# design.net
KiCad netlist of a schematic drawn in EasyEDA Pro
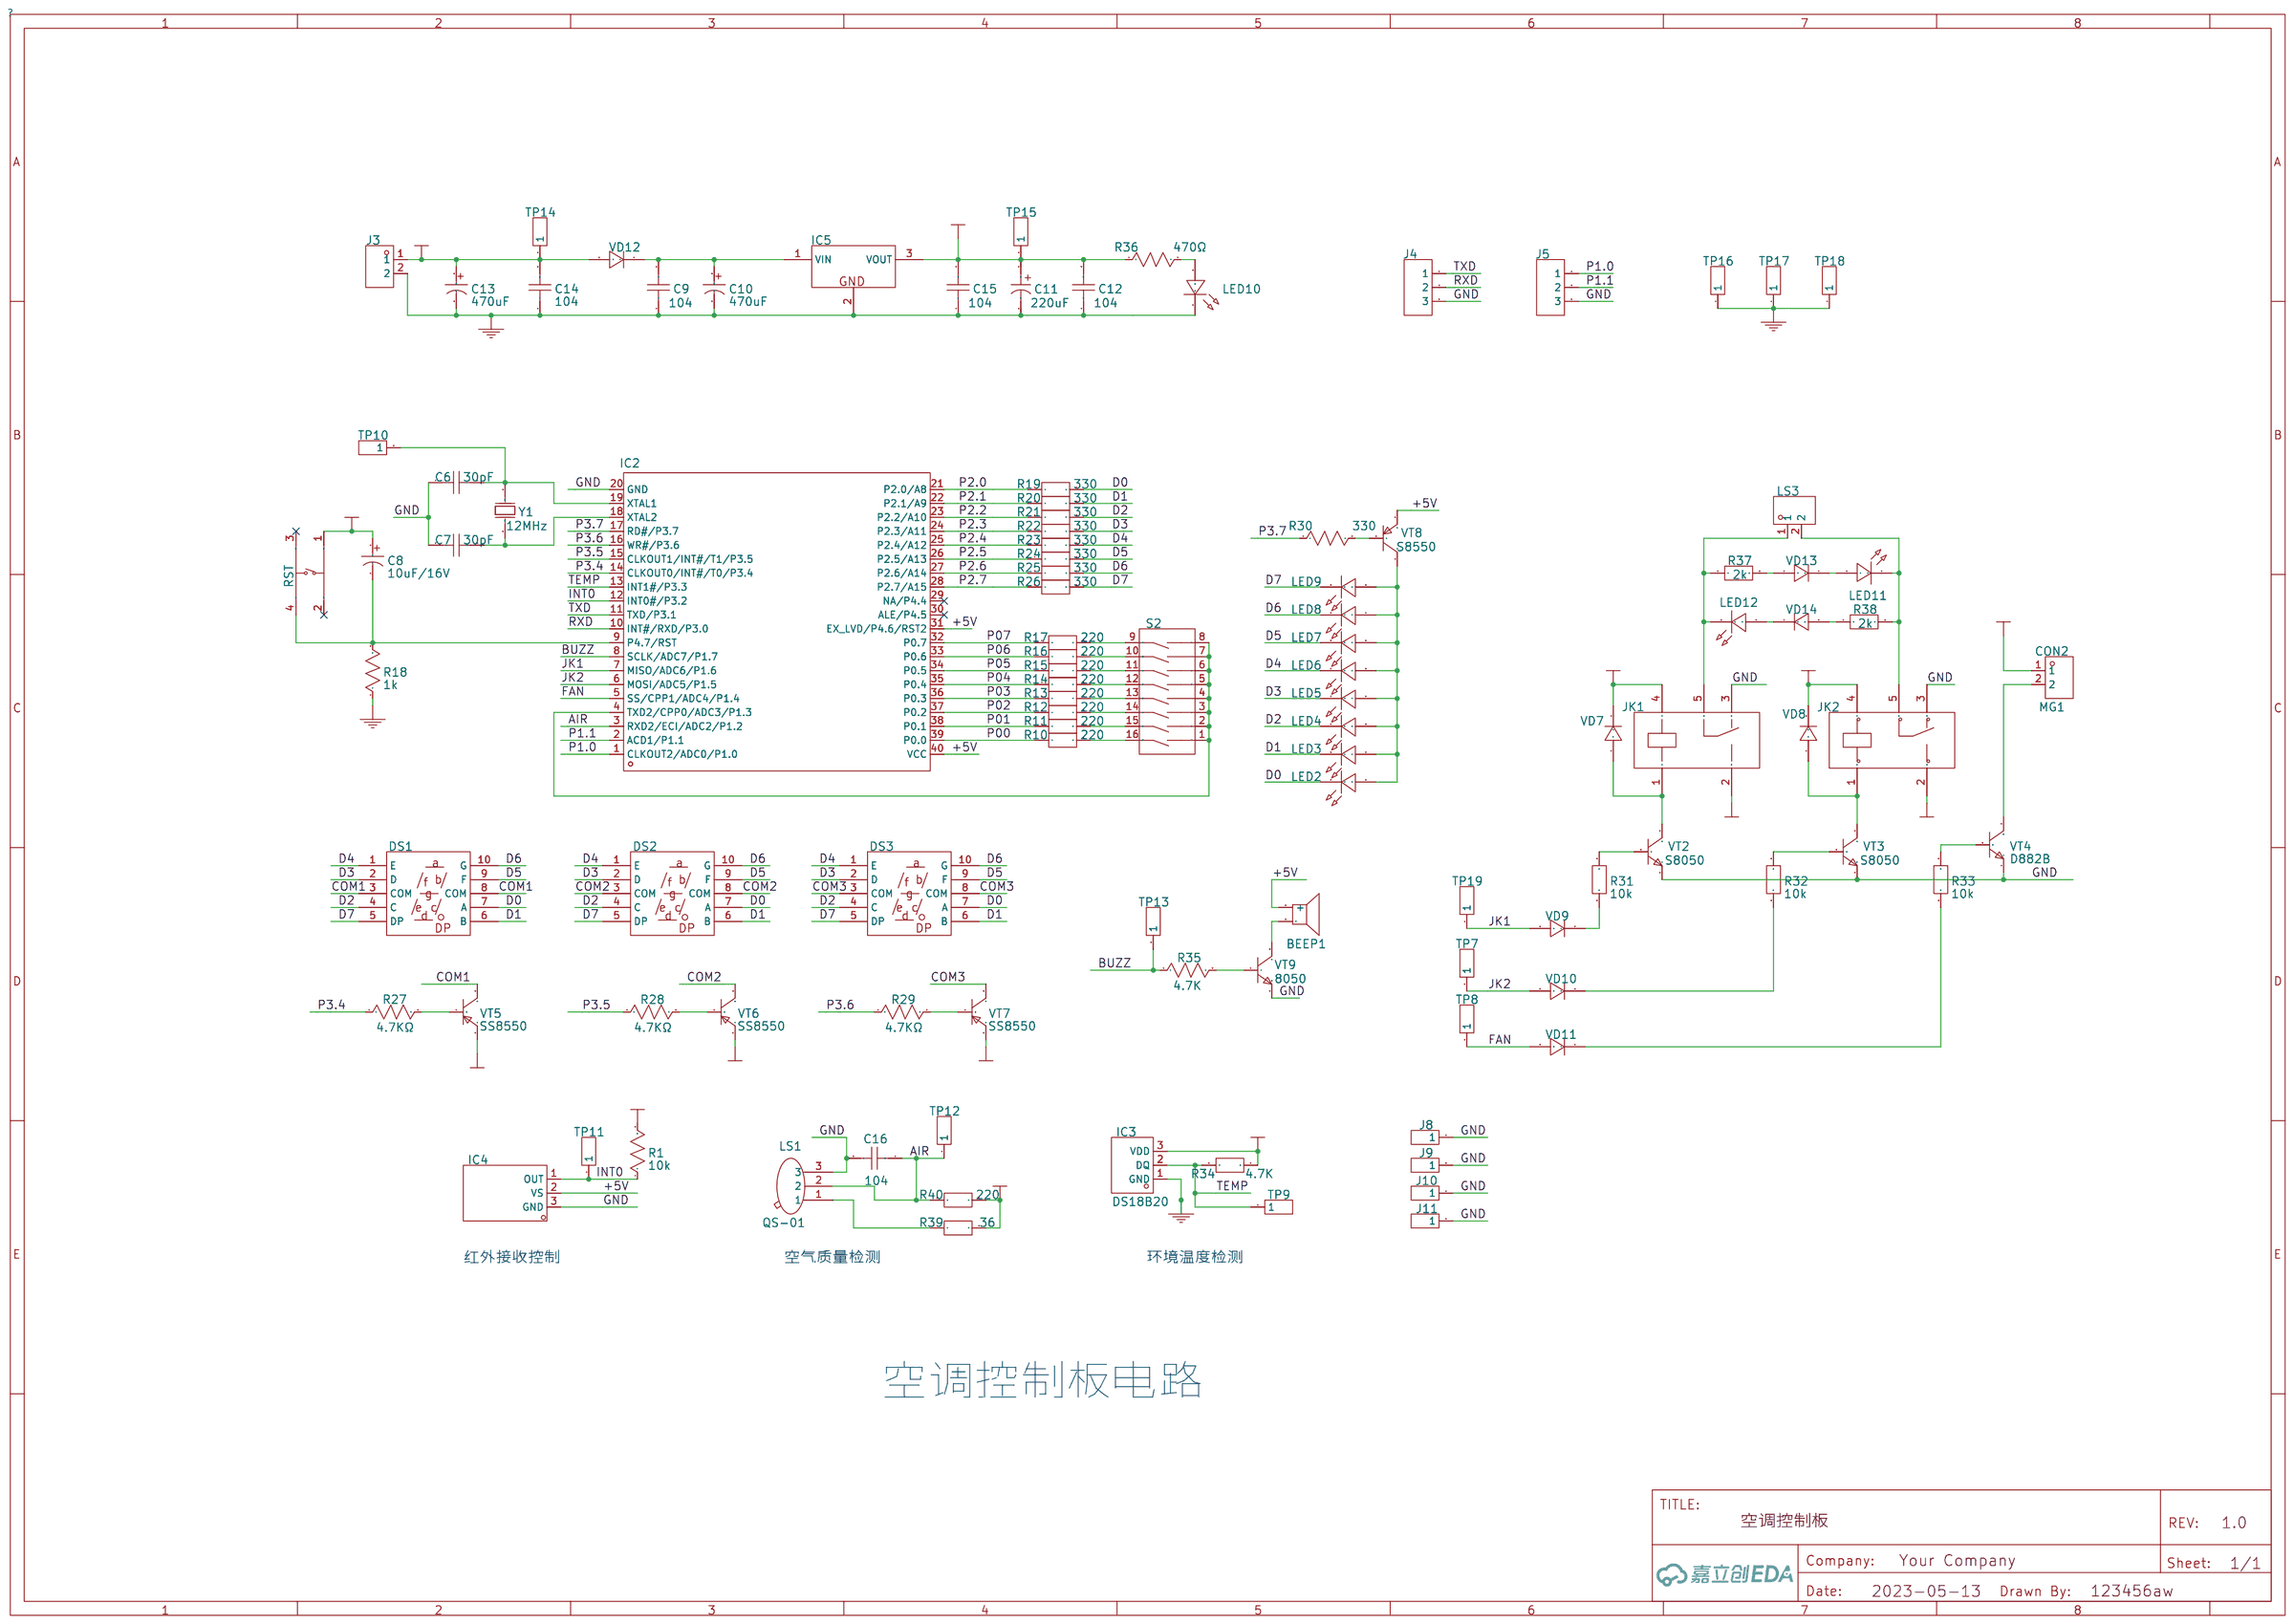
[diagram p0: schematic sheet]

(export (version "E")
  (design (tool "Eeschema 10.0.6"))
  (components
    (comp (ref "BEEP1")
      (value "TMB12A05")
      (footprint "easyedapro:BUZ-TH_BD12.0-P7.60-D0.6-FD")
      (fields (field (name "Manufacturer") "华能"))
      (libsource (lib "easyedapro") (part "TMB12A05"))
    )
    (comp (ref "C6")
      (value "30pF")
      (footprint "easyedapro:C0805")
      (libsource (lib "easyedapro") (part "30pF"))
    )
    (comp (ref "C7")
      (value "30pF")
      (footprint "easyedapro:C0805")
      (libsource (lib "easyedapro") (part "30pF"))
    )
    (comp (ref "C8")
      (value "10uF/16V")
      (footprint "easyedapro:CAP-TH_BD5.0-P2.5-D0.5-FD")
      (fields
        (field (name "Manufacturer Part") "RL1C100MC110A00CV0")
        (field (name "Manufacturer") "HUAWEI(华威集团)")
      )
      (libsource (lib "easyedapro") (part "10uF/16V"))
    )
    (comp (ref "C9") (value "104") (footprint "easyedapro:C0805") (libsource (lib "easyedapro") (part "104")))
    (comp (ref "C10")
      (value "470uF")
      (footprint "easyedapro:CAP-TH_BD10.0-P5.00-D1.0-FD")
      (fields
        (field (name "Manufacturer Part") "KM477M050G20RR0VH2FP0")
        (field (name "Manufacturer") "CX(承兴)")
      )
      (libsource (lib "easyedapro") (part "470uF"))
    )
    (comp (ref "C11")
      (value "220uF")
      (footprint "easyedapro:CAP-TH_BD8.0-P3.50-D0.6-FD_1")
      (fields (field (name "Manufacturer Part") "220uF/35V"))
      (libsource (lib "easyedapro") (part "220uF"))
    )
    (comp (ref "C12")
      (value "104")
      (footprint "easyedapro:C0805")
      (libsource (lib "easyedapro") (part "104"))
    )
    (comp (ref "C13")
      (value "470uF")
      (footprint "easyedapro:CAP-TH_BD10.0-P5.00-D1.0-FD")
      (fields
        (field (name "Manufacturer Part") "KM477M050G20RR0VH2FP0")
        (field (name "Manufacturer") "CX(承兴)")
      )
      (libsource (lib "easyedapro") (part "470uF"))
    )
    (comp (ref "C14")
      (value "104")
      (footprint "easyedapro:C0805")
      (libsource (lib "easyedapro") (part "104"))
    )
    (comp (ref "C15")
      (value "104")
      (footprint "easyedapro:C0805")
      (libsource (lib "easyedapro") (part "104"))
    )
    (comp (ref "C16")
      (value "104")
      (footprint "easyedapro:C0805")
      (libsource (lib "easyedapro") (part "104"))
    )
    (comp (ref "CON2")
      (value "MG1")
      (footprint "easyedapro:CONN-TH_XY301V-A-5.0-2P")
      (fields
        (field (name "Manufacturer Part") "XY301V-A-5.0-2P")
        (field (name "Manufacturer") "XINLAIYA(新莱亚)")
      )
      (libsource (lib "easyedapro") (part "MG1"))
    )
    (comp (ref "DS1")
      (value "FJ5101BH")
      (footprint "easyedapro:LED-SEG-TH_FJ5101BH")
      (fields (field (name "Manufacturer") "志浩"))
      (libsource (lib "easyedapro") (part "FJ5101BH"))
    )
    (comp (ref "DS2")
      (value "FJ5101BH")
      (footprint "easyedapro:LED-SEG-TH_FJ5101BH")
      (fields (field (name "Manufacturer") "志浩"))
      (libsource (lib "easyedapro") (part "FJ5101BH"))
    )
    (comp (ref "DS3")
      (value "FJ5101BH")
      (footprint "easyedapro:LED-SEG-TH_FJ5101BH")
      (fields (field (name "Manufacturer") "志浩"))
      (libsource (lib "easyedapro") (part "FJ5101BH"))
    )
    (comp (ref "IC2")
      (value "STC12C5A32S2")
      (footprint "easyedapro:DIP-40_L52.3-W13.9-P2.54-LS15.2-BL")
      (fields
        (field (name "Manufacturer Part") "STC12C5A32S2-35I-PDIP40")
        (field (name "Manufacturer") "STC(宏晶)")
      )
      (libsource (lib "easyedapro") (part "STC12C5A32S2"))
    )
    (comp (ref "IC3")
      (value "DS18B20")
      (footprint "easyedapro:TO-92-3_L4.9-W3.7-P1.27-L")
      (fields (field (name "Manufacturer") "UMW(广东友台半导体)"))
      (libsource (lib "easyedapro") (part "DS18B20"))
    )
    (comp (ref "IC4")
      (value "TSOP31256")
      (footprint "easyedapro:红外接收管封装")
      (fields (field (name "Manufacturer") "VISHAY(威世)"))
      (libsource (lib "easyedapro") (part "TSOP31256"))
    )
    (comp (ref "IC5")
      (value "LM7805CT_C5444281")
      (footprint "easyedapro:三端稳压器LM7805")
      (fields (field (name "Manufacturer Part") "LM7805CT") (field (name "Manufacturer") "Siproin(上海矽朋)"))
      (libsource (lib "easyedapro") (part "LM7805CT_C5444281"))
    )
    (comp (ref "J3")
      (value "GND   +12V")
      (footprint "easyedapro:CONN-TH_XY301V-A-5.0-2P")
      (fields
        (field (name "Manufacturer Part") "XY301V-A-5.0-2P")
        (field (name "Manufacturer") "XINLAIYA(新莱亚)")
      )
      (libsource (lib "easyedapro") (part "GND   +12V"))
    )
    (comp (ref "J4")
      (value "TXD RXD GND")
      (footprint "easyedapro:HDR-F-2.54_1X3")
      (libsource (lib "easyedapro") (part "TXD RXD GND"))
    )
    (comp (ref "J5")
      (value "HDR-F-2.54_1x3")
      (footprint "easyedapro:HDR-F-2.54_1X3")
      (libsource (lib "easyedapro") (part "HDR-F-2.54_1x3"))
    )
    (comp (ref "J8") (value "RS") (footprint "easyedapro:焊盘M3") (libsource (lib "easyedapro") (part "RS")))
    (comp (ref "J9") (value "RS") (footprint "easyedapro:焊盘M3") (libsource (lib "easyedapro") (part "RS")))
    (comp (ref "J10") (value "RS") (footprint "easyedapro:焊盘M3") (libsource (lib "easyedapro") (part "RS")))
    (comp (ref "J11") (value "RS") (footprint "easyedapro:焊盘M3") (libsource (lib "easyedapro") (part "RS")))
    (comp (ref "JK1")
      (value "SRD-12VDC-SL-C")
      (footprint "easyedapro:RELAY-TH_SRD-XXVDC-XL-C")
      (fields (field (name "Manufacturer") "松乐"))
      (libsource (lib "easyedapro") (part "SRD-12VDC-SL-C"))
    )
    (comp (ref "JK2")
      (value "SRD-12VDC-SL-C")
      (footprint "easyedapro:RELAY-TH_SRD-XXVDC-XL-C")
      (fields (field (name "Manufacturer") "松乐"))
      (libsource (lib "") (part "SRD-12VDC-SL-C_1"))
    )
    (comp (ref "LED2")
      (value "LED-0805_R")
      (footprint "easyedapro:LED0805_RED")
      (fields
        (field (name "Manufacturer Part") "17-21SURC/S530-A3/TR8")
        (field (name "Manufacturer") "EVERLIGHT(台湾亿光)")
      )
      (libsource (lib "easyedapro") (part "LED-0805_R"))
    )
    (comp (ref "LED3")
      (value "LED-0805_R")
      (footprint "easyedapro:LED0805_RED")
      (fields
        (field (name "Manufacturer Part") "17-21SURC/S530-A3/TR8")
        (field (name "Manufacturer") "EVERLIGHT(台湾亿光)")
      )
      (libsource (lib "easyedapro") (part "LED-0805_R"))
    )
    (comp (ref "LED4")
      (value "LED-0805_R")
      (footprint "easyedapro:LED0805_RED")
      (fields
        (field (name "Manufacturer Part") "17-21SURC/S530-A3/TR8")
        (field (name "Manufacturer") "EVERLIGHT(台湾亿光)")
      )
      (libsource (lib "easyedapro") (part "LED-0805_R"))
    )
    (comp (ref "LED5")
      (value "LED-0805_R")
      (footprint "easyedapro:LED0805_RED")
      (fields
        (field (name "Manufacturer Part") "17-21SURC/S530-A3/TR8")
        (field (name "Manufacturer") "EVERLIGHT(台湾亿光)")
      )
      (libsource (lib "easyedapro") (part "LED-0805_R"))
    )
    (comp (ref "LED6")
      (value "LED-0805_R")
      (footprint "easyedapro:LED0805_RED")
      (fields
        (field (name "Manufacturer Part") "17-21SURC/S530-A3/TR8")
        (field (name "Manufacturer") "EVERLIGHT(台湾亿光)")
      )
      (libsource (lib "easyedapro") (part "LED-0805_R"))
    )
    (comp (ref "LED7")
      (value "LED-0805_R")
      (footprint "easyedapro:LED0805_RED")
      (fields
        (field (name "Manufacturer Part") "17-21SURC/S530-A3/TR8")
        (field (name "Manufacturer") "EVERLIGHT(台湾亿光)")
      )
      (libsource (lib "easyedapro") (part "LED-0805_R"))
    )
    (comp (ref "LED8")
      (value "LED-0805_R")
      (footprint "easyedapro:LED0805_RED")
      (fields
        (field (name "Manufacturer Part") "17-21SURC/S530-A3/TR8")
        (field (name "Manufacturer") "EVERLIGHT(台湾亿光)")
      )
      (libsource (lib "easyedapro") (part "LED-0805_R"))
    )
    (comp (ref "LED9")
      (value "LED-0805_R")
      (footprint "easyedapro:LED0805_RED")
      (fields
        (field (name "Manufacturer Part") "17-21SURC/S530-A3/TR8")
        (field (name "Manufacturer") "EVERLIGHT(台湾亿光)")
      )
      (libsource (lib "easyedapro") (part "LED-0805_R"))
    )
    (comp (ref "LED10")
      (value "LED-0805_R")
      (footprint "easyedapro:LED0805_RED")
      (fields
        (field (name "Manufacturer Part") "17-21SURC/S530-A3/TR8")
        (field (name "Manufacturer") "EVERLIGHT(台湾亿光)")
      )
      (libsource (lib "easyedapro") (part "LED-0805_R"))
    )
    (comp (ref "LED11")
      (value "LED-0805_R")
      (footprint "easyedapro:LED0805_RED")
      (fields
        (field (name "Manufacturer Part") "17-21SURC/S530-A3/TR8")
        (field (name "Manufacturer") "EVERLIGHT(台湾亿光)")
      )
      (libsource (lib "easyedapro") (part "LED-0805_R"))
    )
    (comp (ref "LED12")
      (value "LED-0805_R")
      (footprint "easyedapro:LED0805_RED")
      (fields
        (field (name "Manufacturer Part") "17-21SURC/S530-A3/TR8")
        (field (name "Manufacturer") "EVERLIGHT(台湾亿光)")
      )
      (libsource (lib "easyedapro") (part "LED-0805_R"))
    )
    (comp (ref "LS1")
      (value "QS-01")
      (footprint "easyedapro:空气质量传感器")
      (fields (field (name "Manufacturer Part") "MP901") (field (name "Manufacturer") "Winsen(炜盛)"))
      (libsource (lib "easyedapro") (part "QS-01"))
    )
    (comp (ref "LS3")
      (value "XY301V-A-5.0-2P")
      (footprint "easyedapro:CONN-TH_XY301V-A-5.0-2P")
      (fields (field (name "Manufacturer") "XINLAIYA(新莱亚)"))
      (libsource (lib "easyedapro") (part "XY301V-A-5.0-2P"))
    )
    (comp (ref "R1") (value "10k") (footprint "easyedapro:R0805") (libsource (lib "") (part "10k_1")))
    (comp (ref "R10")
      (value "220")
      (footprint "easyedapro:R0805")
      (libsource (lib "easyedapro") (part "220"))
    )
    (comp (ref "R11")
      (value "220")
      (footprint "easyedapro:R0805")
      (libsource (lib "easyedapro") (part "220"))
    )
    (comp (ref "R12")
      (value "220")
      (footprint "easyedapro:R0805")
      (libsource (lib "easyedapro") (part "220"))
    )
    (comp (ref "R13")
      (value "220")
      (footprint "easyedapro:R0805")
      (libsource (lib "easyedapro") (part "220"))
    )
    (comp (ref "R14")
      (value "220")
      (footprint "easyedapro:R0805")
      (libsource (lib "easyedapro") (part "220"))
    )
    (comp (ref "R15")
      (value "220")
      (footprint "easyedapro:R0805")
      (libsource (lib "easyedapro") (part "220"))
    )
    (comp (ref "R16")
      (value "220")
      (footprint "easyedapro:R0805")
      (libsource (lib "easyedapro") (part "220"))
    )
    (comp (ref "R17")
      (value "220")
      (footprint "easyedapro:R0805")
      (libsource (lib "easyedapro") (part "220"))
    )
    (comp (ref "R18") (value "1k") (footprint "easyedapro:R0805") (libsource (lib "easyedapro") (part "1k")))
    (comp (ref "R19")
      (value "330")
      (footprint "easyedapro:R0805")
      (libsource (lib "easyedapro") (part "330"))
    )
    (comp (ref "R20")
      (value "330")
      (footprint "easyedapro:R0805")
      (libsource (lib "easyedapro") (part "330"))
    )
    (comp (ref "R21")
      (value "330")
      (footprint "easyedapro:R0805")
      (libsource (lib "easyedapro") (part "330"))
    )
    (comp (ref "R22")
      (value "330")
      (footprint "easyedapro:R0805")
      (libsource (lib "easyedapro") (part "330"))
    )
    (comp (ref "R23")
      (value "330")
      (footprint "easyedapro:R0805")
      (libsource (lib "easyedapro") (part "330"))
    )
    (comp (ref "R24")
      (value "330")
      (footprint "easyedapro:R0805")
      (libsource (lib "easyedapro") (part "330"))
    )
    (comp (ref "R25")
      (value "330")
      (footprint "easyedapro:R0805")
      (libsource (lib "easyedapro") (part "330"))
    )
    (comp (ref "R26")
      (value "330")
      (footprint "easyedapro:R0805")
      (libsource (lib "easyedapro") (part "330"))
    )
    (comp (ref "R27")
      (value "4.7KΩ")
      (footprint "easyedapro:R0805")
      (libsource (lib "easyedapro") (part "4.7KΩ"))
    )
    (comp (ref "R28")
      (value "4.7KΩ")
      (footprint "easyedapro:R0805")
      (libsource (lib "easyedapro") (part "4.7KΩ"))
    )
    (comp (ref "R29")
      (value "4.7KΩ")
      (footprint "easyedapro:R0805")
      (libsource (lib "easyedapro") (part "4.7KΩ"))
    )
    (comp (ref "R30") (value "330") (footprint "easyedapro:R0805") (libsource (lib "") (part "330_1")))
    (comp (ref "R31")
      (value "10k")
      (footprint "easyedapro:R0805")
      (libsource (lib "easyedapro") (part "10k"))
    )
    (comp (ref "R32")
      (value "10k")
      (footprint "easyedapro:R0805")
      (libsource (lib "easyedapro") (part "10k"))
    )
    (comp (ref "R33")
      (value "10k")
      (footprint "easyedapro:R0805")
      (libsource (lib "easyedapro") (part "10k"))
    )
    (comp (ref "R34") (value "4.7K") (footprint "easyedapro:R0805") (libsource (lib "") (part "4.7K_1")))
    (comp (ref "R35")
      (value "4.7K")
      (footprint "easyedapro:R0805")
      (libsource (lib "easyedapro") (part "4.7K"))
    )
    (comp (ref "R36")
      (value "470Ω")
      (footprint "easyedapro:R0805")
      (libsource (lib "easyedapro") (part "470Ω"))
    )
    (comp (ref "R37") (value "2k") (footprint "easyedapro:R0805") (libsource (lib "easyedapro") (part "2k")))
    (comp (ref "R38") (value "2k") (footprint "easyedapro:R0805") (libsource (lib "easyedapro") (part "2k")))
    (comp (ref "R39")
      (value "36")
      (footprint "easyedapro:R2010")
      (fields
        (field (name "Manufacturer Part") "201007F360JT4E")
        (field (name "Manufacturer") "UNI-ROYAL(厚声)")
      )
      (libsource (lib "easyedapro") (part "36"))
    )
    (comp (ref "R40")
      (value "220")
      (footprint "easyedapro:R0805")
      (libsource (lib "easyedapro") (part "220"))
    )
    (comp (ref "RST")
      (value "TS665CJ")
      (footprint "easyedapro:SW-TH_4P-L6.0-W6.0-P4.50-LS6.5")
      (fields (field (name "Manufacturer") "SHOU HAN(首韩)"))
      (libsource (lib "easyedapro") (part "TS665CJ"))
    )
    (comp (ref "S2")
      (value "2.54插件8位拨码开关")
      (footprint "easyedapro:SW-TH_16P-L21.9-W9.9-P2.54-LS7.8")
      (libsource (lib "easyedapro") (part "2.54插件8位拨码开关"))
    )
    (comp (ref "TP7")
      (value "HDR-M-2.54_1x1")
      (footprint "easyedapro:HDR-M-2.54_1X1")
      (libsource (lib "easyedapro") (part "HDR-M-2.54_1x1"))
    )
    (comp (ref "TP8")
      (value "HDR-M-2.54_1x1")
      (footprint "easyedapro:HDR-M-2.54_1X1")
      (libsource (lib "easyedapro") (part "HDR-M-2.54_1x1"))
    )
    (comp (ref "TP9")
      (value "HDR-M-2.54_1x1")
      (footprint "easyedapro:HDR-M-2.54_1X1")
      (libsource (lib "easyedapro") (part "HDR-M-2.54_1x1"))
    )
    (comp (ref "TP10")
      (value "HDR-M-2.54_1x1")
      (footprint "easyedapro:HDR-M-2.54_1X1")
      (libsource (lib "easyedapro") (part "HDR-M-2.54_1x1"))
    )
    (comp (ref "TP11")
      (value "HDR-M-2.54_1x1")
      (footprint "easyedapro:HDR-M-2.54_1X1")
      (libsource (lib "easyedapro") (part "HDR-M-2.54_1x1"))
    )
    (comp (ref "TP12")
      (value "HDR-M-2.54_1x1")
      (footprint "easyedapro:HDR-M-2.54_1X1")
      (libsource (lib "easyedapro") (part "HDR-M-2.54_1x1"))
    )
    (comp (ref "TP13")
      (value "HDR-M-2.54_1x1")
      (footprint "easyedapro:HDR-M-2.54_1X1")
      (libsource (lib "easyedapro") (part "HDR-M-2.54_1x1"))
    )
    (comp (ref "TP14")
      (value "HDR-M-2.54_1x1")
      (footprint "easyedapro:HDR-M-2.54_1X1")
      (libsource (lib "easyedapro") (part "HDR-M-2.54_1x1"))
    )
    (comp (ref "TP15")
      (value "HDR-M-2.54_1x1")
      (footprint "easyedapro:HDR-M-2.54_1X1")
      (libsource (lib "easyedapro") (part "HDR-M-2.54_1x1"))
    )
    (comp (ref "TP16")
      (value "HDR-M-2.54_1x1")
      (footprint "easyedapro:HDR-M-2.54_1X1")
      (libsource (lib "easyedapro") (part "HDR-M-2.54_1x1"))
    )
    (comp (ref "TP17")
      (value "HDR-M-2.54_1x1")
      (footprint "easyedapro:HDR-M-2.54_1X1")
      (libsource (lib "easyedapro") (part "HDR-M-2.54_1x1"))
    )
    (comp (ref "TP18")
      (value "HDR-M-2.54_1x1")
      (footprint "easyedapro:HDR-M-2.54_1X1")
      (libsource (lib "easyedapro") (part "HDR-M-2.54_1x1"))
    )
    (comp (ref "TP19")
      (value "HDR-M-2.54_1x1")
      (footprint "easyedapro:HDR-M-2.54_1X1")
      (libsource (lib "easyedapro") (part "HDR-M-2.54_1x1"))
    )
    (comp (ref "VD7")
      (value "1N4007G_C189227")
      (footprint "easyedapro:DO-41_BD2.4-L4.7-P8.70-D0.9-RD")
      (fields (field (name "Manufacturer Part") "1N4007G") (field (name "Manufacturer") "迪一"))
      (libsource (lib "easyedapro") (part "1N4007G_C189227"))
    )
    (comp (ref "VD8")
      (value "1N4007G_C189227")
      (footprint "easyedapro:DO-41_BD2.4-L4.7-P8.70-D0.9-RD")
      (fields (field (name "Manufacturer Part") "1N4007G") (field (name "Manufacturer") "迪一"))
      (libsource (lib "easyedapro") (part "1N4007G_C189227"))
    )
    (comp (ref "VD9")
      (value "1N4007G_C189227")
      (footprint "easyedapro:DO-41_BD2.4-L4.7-P8.70-D0.9-RD")
      (fields (field (name "Manufacturer Part") "1N4007G") (field (name "Manufacturer") "迪一"))
      (libsource (lib "easyedapro") (part "1N4007G_C189227"))
    )
    (comp (ref "VD10")
      (value "1N4007G_C189227")
      (footprint "easyedapro:DO-41_BD2.4-L4.7-P8.70-D0.9-RD")
      (fields (field (name "Manufacturer Part") "1N4007G") (field (name "Manufacturer") "迪一"))
      (libsource (lib "easyedapro") (part "1N4007G_C189227"))
    )
    (comp (ref "VD11")
      (value "1N4007G_C189227")
      (footprint "easyedapro:DO-41_BD2.4-L4.7-P8.70-D0.9-RD")
      (fields (field (name "Manufacturer Part") "1N4007G") (field (name "Manufacturer") "迪一"))
      (libsource (lib "easyedapro") (part "1N4007G_C189227"))
    )
    (comp (ref "VD12")
      (value "1N4007G_C189227")
      (footprint "easyedapro:DO-41_BD2.4-L4.7-P8.70-D0.9-RD")
      (fields (field (name "Manufacturer Part") "1N4007G") (field (name "Manufacturer") "迪一"))
      (libsource (lib "easyedapro") (part "1N4007G_C189227"))
    )
    (comp (ref "VD13")
      (value "1N4007G_C189227")
      (footprint "easyedapro:DO-41_BD2.4-L4.7-P8.70-D0.9-RD")
      (fields (field (name "Manufacturer Part") "1N4007G") (field (name "Manufacturer") "迪一"))
      (libsource (lib "easyedapro") (part "1N4007G_C189227"))
    )
    (comp (ref "VD14")
      (value "1N4007G_C189227")
      (footprint "easyedapro:DO-41_BD2.4-L4.7-P8.70-D0.9-RD")
      (fields (field (name "Manufacturer Part") "1N4007G") (field (name "Manufacturer") "迪一"))
      (libsource (lib "easyedapro") (part "1N4007G_C189227"))
    )
    (comp (ref "VT2")
      (value "S8050")
      (footprint "easyedapro:SOT-23-3_L2.9-W1.6-P1.90-LS2.8-BR")
      (fields (field (name "Manufacturer") "Hottech(合科泰)"))
      (libsource (lib "easyedapro") (part "S8050"))
    )
    (comp (ref "VT3")
      (value "S8050")
      (footprint "easyedapro:SOT-23-3_L2.9-W1.6-P1.90-LS2.8-BR")
      (fields (field (name "Manufacturer") "Hottech(合科泰)"))
      (libsource (lib "easyedapro") (part "S8050"))
    )
    (comp (ref "VT4")
      (value "D882B")
      (footprint "easyedapro:TO-126_L7.8-W2.7-P2.30-L")
      (fields (field (name "Manufacturer") "FeiHong(飞虹)"))
      (libsource (lib "easyedapro") (part "D882B"))
    )
    (comp (ref "VT5")
      (value "SS8550")
      (footprint "easyedapro:SOT-23-3_L2.9-W1.3-P1.90-LS2.4-BR")
      (fields (field (name "Manufacturer Part") "SS8550-MS") (field (name "Manufacturer") "MSKSEMI(美森科)"))
      (libsource (lib "easyedapro") (part "SS8550"))
    )
    (comp (ref "VT6")
      (value "SS8550")
      (footprint "easyedapro:SOT-23-3_L2.9-W1.3-P1.90-LS2.4-BR")
      (fields (field (name "Manufacturer Part") "SS8550-MS") (field (name "Manufacturer") "MSKSEMI(美森科)"))
      (libsource (lib "easyedapro") (part "SS8550"))
    )
    (comp (ref "VT7")
      (value "SS8550")
      (footprint "easyedapro:SOT-23-3_L2.9-W1.3-P1.90-LS2.4-BR")
      (fields (field (name "Manufacturer Part") "SS8550-MS") (field (name "Manufacturer") "MSKSEMI(美森科)"))
      (libsource (lib "easyedapro") (part "SS8550"))
    )
    (comp (ref "VT8")
      (value "S8550")
      (footprint "easyedapro:SOT-23-3_L2.9-W1.6-P1.90-LS2.8-BR")
      (fields (field (name "Manufacturer") "CJ(江苏长电/长晶)"))
      (libsource (lib "easyedapro") (part "S8550"))
    )
    (comp (ref "VT9")
      (value "8050")
      (footprint "easyedapro:SOT-23-3_L2.9-W1.6-P1.90-LS2.8-BR")
      (fields (field (name "Manufacturer Part") "S9013") (field (name "Manufacturer") "CJ(江苏长电/长晶)"))
      (libsource (lib "easyedapro") (part "8050"))
    )
    (comp (ref "Y1")
      (value "12MHz")
      (footprint "easyedapro:HC-49US_L11.5-W4.5-P4.88")
      (fields (field (name "Manufacturer Part") "X49SD12MSD2SC") (field (name "Manufacturer") "YXC(扬兴晶振)"))
      (libsource (lib "easyedapro") (part "12MHz"))
    )
  )
  (nets
    (net (code "1") (name "+5V") (class "Default")
      (node (ref "BEEP1") (pin "1") (pinfunction "+_1") (pintype "input"))
      (node (ref "C11") (pin "1") (pinfunction "1_1") (pintype "input"))
      (node (ref "C12") (pin "2") (pinfunction "2_2") (pintype "input"))
      (node (ref "C15") (pin "2") (pinfunction "2_2") (pintype "input"))
      (node (ref "C8") (pin "1") (pinfunction "1_1") (pintype "input"))
      (node (ref "IC2") (pin "31") (pinfunction "EX_LVD/P4.6/RST2_31") (pintype "input"))
      (node (ref "IC2") (pin "40") (pinfunction "VCC_40") (pintype "input"))
      (node (ref "IC3") (pin "3") (pinfunction "VDD_3") (pintype "input"))
      (node (ref "IC4") (pin "2") (pinfunction "VS_2") (pintype "input"))
      (node (ref "IC5") (pin "3") (pinfunction "VOUT_3") (pintype "input"))
      (node (ref "R1") (pin "2") (pinfunction "2_2") (pintype "input"))
      (node (ref "R34") (pin "1") (pinfunction "1_1") (pintype "input"))
      (node (ref "R36") (pin "1") (pinfunction "1_1") (pintype "input"))
      (node (ref "R39") (pin "2") (pinfunction "2_2") (pintype "input"))
      (node (ref "R40") (pin "2") (pinfunction "2_2") (pintype "input"))
      (node (ref "RST") (pin "1") (pinfunction "A_1") (pintype "input"))
      (node (ref "TP15") (pin "1") (pinfunction "1_1") (pintype "input"))
      (node (ref "VT5") (pin "2") (pinfunction "E_2") (pintype "input"))
      (node (ref "VT6") (pin "2") (pinfunction "E_2") (pintype "input"))
      (node (ref "VT7") (pin "2") (pinfunction "E_2") (pintype "input"))
      (node (ref "VT8") (pin "2") (pinfunction "2_2") (pintype "input"))
    )
    (net (code "2") (name "+12V") (class "Default")
      (node (ref "C13") (pin "1") (pinfunction "1_1") (pintype "input"))
      (node (ref "C14") (pin "2") (pinfunction "2_2") (pintype "input"))
      (node (ref "CON2") (pin "1") (pinfunction "1_1") (pintype "input"))
      (node (ref "J3") (pin "1") (pinfunction "1_1") (pintype "input"))
      (node (ref "JK1") (pin "2") (pinfunction "2_2") (pintype "input"))
      (node (ref "JK1") (pin "4") (pinfunction "4_4") (pintype "input"))
      (node (ref "JK2") (pin "2") (pinfunction "2_2") (pintype "input"))
      (node (ref "JK2") (pin "4") (pinfunction "4_4") (pintype "input"))
      (node (ref "TP14") (pin "1") (pinfunction "1_1") (pintype "input"))
      (node (ref "VD12") (pin "2") (pinfunction "2_2") (pintype "input"))
      (node (ref "VD7") (pin "1") (pinfunction "1_1") (pintype "input"))
      (node (ref "VD8") (pin "1") (pinfunction "1_1") (pintype "input"))
    )
    (net (code "3") (name "/AIR") (class "Default")
      (node (ref "C16") (pin "1") (pinfunction "1_1") (pintype "input"))
      (node (ref "IC2") (pin "3") (pinfunction "RXD2/ECI/ADC2/P1.2_3") (pintype "input"))
      (node (ref "LS1") (pin "2") (pinfunction "2_2") (pintype "input"))
      (node (ref "R40") (pin "1") (pinfunction "1_1") (pintype "input"))
      (node (ref "TP12") (pin "1") (pinfunction "1_1") (pintype "input"))
    )
    (net (code "4") (name "/BUZZ") (class "Default")
      (node (ref "IC2") (pin "8") (pinfunction "SCLK/ADC7/P1.7_8") (pintype "input"))
      (node (ref "R35") (pin "1") (pinfunction "1_1") (pintype "input"))
      (node (ref "TP13") (pin "1") (pinfunction "1_1") (pintype "input"))
    )
    (net (code "5") (name "/COM1") (class "Default")
      (node (ref "DS1") (pin "3") (pinfunction "COM_3") (pintype "input"))
      (node (ref "DS1") (pin "8") (pinfunction "COM_8") (pintype "input"))
      (node (ref "VT5") (pin "3") (pinfunction "C_3") (pintype "input"))
    )
    (net (code "6") (name "/COM2") (class "Default")
      (node (ref "DS2") (pin "3") (pinfunction "COM_3") (pintype "input"))
      (node (ref "DS2") (pin "8") (pinfunction "COM_8") (pintype "input"))
      (node (ref "VT6") (pin "3") (pinfunction "C_3") (pintype "input"))
    )
    (net (code "7") (name "/COM3") (class "Default")
      (node (ref "DS3") (pin "3") (pinfunction "COM_3") (pintype "input"))
      (node (ref "DS3") (pin "8") (pinfunction "COM_8") (pintype "input"))
      (node (ref "VT7") (pin "3") (pinfunction "C_3") (pintype "input"))
    )
    (net (code "8") (name "/D0") (class "Default")
      (node (ref "DS1") (pin "7") (pinfunction "A_7") (pintype "input"))
      (node (ref "DS2") (pin "7") (pinfunction "A_7") (pintype "input"))
      (node (ref "DS3") (pin "7") (pinfunction "A_7") (pintype "input"))
      (node (ref "LED2") (pin "2") (pinfunction "2_2") (pintype "input"))
      (node (ref "R19") (pin "2") (pinfunction "2_2") (pintype "input"))
    )
    (net (code "9") (name "/D1") (class "Default")
      (node (ref "DS1") (pin "6") (pinfunction "B_6") (pintype "input"))
      (node (ref "DS2") (pin "6") (pinfunction "B_6") (pintype "input"))
      (node (ref "DS3") (pin "6") (pinfunction "B_6") (pintype "input"))
      (node (ref "LED3") (pin "2") (pinfunction "2_2") (pintype "input"))
      (node (ref "R20") (pin "2") (pinfunction "2_2") (pintype "input"))
    )
    (net (code "10") (name "/D2") (class "Default")
      (node (ref "DS1") (pin "4") (pinfunction "C_4") (pintype "input"))
      (node (ref "DS2") (pin "4") (pinfunction "C_4") (pintype "input"))
      (node (ref "DS3") (pin "4") (pinfunction "C_4") (pintype "input"))
      (node (ref "LED4") (pin "2") (pinfunction "2_2") (pintype "input"))
      (node (ref "R21") (pin "2") (pinfunction "2_2") (pintype "input"))
    )
    (net (code "11") (name "/D3") (class "Default")
      (node (ref "DS1") (pin "2") (pinfunction "D_2") (pintype "input"))
      (node (ref "DS2") (pin "2") (pinfunction "D_2") (pintype "input"))
      (node (ref "DS3") (pin "2") (pinfunction "D_2") (pintype "input"))
      (node (ref "LED5") (pin "2") (pinfunction "2_2") (pintype "input"))
      (node (ref "R22") (pin "2") (pinfunction "2_2") (pintype "input"))
    )
    (net (code "12") (name "/D4") (class "Default")
      (node (ref "DS1") (pin "1") (pinfunction "E_1") (pintype "input"))
      (node (ref "DS2") (pin "1") (pinfunction "E_1") (pintype "input"))
      (node (ref "DS3") (pin "1") (pinfunction "E_1") (pintype "input"))
      (node (ref "LED6") (pin "2") (pinfunction "2_2") (pintype "input"))
      (node (ref "R23") (pin "2") (pinfunction "2_2") (pintype "input"))
    )
    (net (code "13") (name "/D5") (class "Default")
      (node (ref "DS1") (pin "9") (pinfunction "F_9") (pintype "input"))
      (node (ref "DS2") (pin "9") (pinfunction "F_9") (pintype "input"))
      (node (ref "DS3") (pin "9") (pinfunction "F_9") (pintype "input"))
      (node (ref "LED7") (pin "2") (pinfunction "2_2") (pintype "input"))
      (node (ref "R24") (pin "2") (pinfunction "2_2") (pintype "input"))
    )
    (net (code "14") (name "/D6") (class "Default")
      (node (ref "DS1") (pin "10") (pinfunction "G_10") (pintype "input"))
      (node (ref "DS2") (pin "10") (pinfunction "G_10") (pintype "input"))
      (node (ref "DS3") (pin "10") (pinfunction "G_10") (pintype "input"))
      (node (ref "LED8") (pin "2") (pinfunction "2_2") (pintype "input"))
      (node (ref "R25") (pin "2") (pinfunction "2_2") (pintype "input"))
    )
    (net (code "15") (name "/D7") (class "Default")
      (node (ref "DS1") (pin "5") (pinfunction "DP_5") (pintype "input"))
      (node (ref "DS2") (pin "5") (pinfunction "DP_5") (pintype "input"))
      (node (ref "DS3") (pin "5") (pinfunction "DP_5") (pintype "input"))
      (node (ref "LED9") (pin "2") (pinfunction "2_2") (pintype "input"))
      (node (ref "R26") (pin "2") (pinfunction "2_2") (pintype "input"))
    )
    (net (code "16") (name "/FAN") (class "Default")
      (node (ref "IC2") (pin "5") (pinfunction "SS/CPP1/ADC4/P1.4_5") (pintype "input"))
      (node (ref "TP8") (pin "1") (pinfunction "1_1") (pintype "input"))
      (node (ref "VD11") (pin "2") (pinfunction "2_2") (pintype "input"))
    )
    (net (code "17") (name "/INT0") (class "Default")
      (node (ref "IC2") (pin "12") (pinfunction "INT0#/P3.2_12") (pintype "input"))
      (node (ref "IC4") (pin "1") (pinfunction "OUT_1") (pintype "input"))
      (node (ref "R1") (pin "1") (pinfunction "1_1") (pintype "input"))
      (node (ref "TP11") (pin "1") (pinfunction "1_1") (pintype "input"))
    )
    (net (code "18") (name "/JK1") (class "Default")
      (node (ref "IC2") (pin "7") (pinfunction "MISO/ADC6/P1.6_7") (pintype "input"))
      (node (ref "TP19") (pin "1") (pinfunction "1_1") (pintype "input"))
      (node (ref "VD9") (pin "2") (pinfunction "2_2") (pintype "input"))
    )
    (net (code "19") (name "/JK2") (class "Default")
      (node (ref "IC2") (pin "6") (pinfunction "MOSI/ADC5/P1.5_6") (pintype "input"))
      (node (ref "TP7") (pin "1") (pinfunction "1_1") (pintype "input"))
      (node (ref "VD10") (pin "2") (pinfunction "2_2") (pintype "input"))
    )
    (net (code "20") (name "/P00") (class "Default")
      (node (ref "IC2") (pin "39") (pinfunction "P0.0_39") (pintype "input"))
      (node (ref "R10") (pin "1") (pinfunction "1_1") (pintype "input"))
    )
    (net (code "21") (name "/P01") (class "Default")
      (node (ref "IC2") (pin "38") (pinfunction "P0.1_38") (pintype "input"))
      (node (ref "R11") (pin "1") (pinfunction "1_1") (pintype "input"))
    )
    (net (code "22") (name "/P1.0") (class "Default")
      (node (ref "IC2") (pin "1") (pinfunction "CLKOUT2/ADC0/P1.0_1") (pintype "input"))
      (node (ref "J5") (pin "1") (pinfunction "1_1") (pintype "input"))
    )
    (net (code "23") (name "/P1.1") (class "Default")
      (node (ref "IC2") (pin "2") (pinfunction "ACD1/P1.1_2") (pintype "input"))
      (node (ref "J5") (pin "2") (pinfunction "2_2") (pintype "input"))
    )
    (net (code "24") (name "/P02") (class "Default")
      (node (ref "IC2") (pin "37") (pinfunction "P0.2_37") (pintype "input"))
      (node (ref "R12") (pin "1") (pinfunction "1_1") (pintype "input"))
    )
    (net (code "25") (name "/P2.0") (class "Default")
      (node (ref "IC2") (pin "21") (pinfunction "P2.0/A8_21") (pintype "input"))
      (node (ref "R19") (pin "1") (pinfunction "1_1") (pintype "input"))
    )
    (net (code "26") (name "/P2.1") (class "Default")
      (node (ref "IC2") (pin "22") (pinfunction "P2.1/A9_22") (pintype "input"))
      (node (ref "R20") (pin "1") (pinfunction "1_1") (pintype "input"))
    )
    (net (code "27") (name "/P2.2") (class "Default")
      (node (ref "IC2") (pin "23") (pinfunction "P2.2/A10_23") (pintype "input"))
      (node (ref "R21") (pin "1") (pinfunction "1_1") (pintype "input"))
    )
    (net (code "28") (name "/P2.3") (class "Default")
      (node (ref "IC2") (pin "24") (pinfunction "P2.3/A11_24") (pintype "input"))
      (node (ref "R22") (pin "1") (pinfunction "1_1") (pintype "input"))
    )
    (net (code "29") (name "/P2.4") (class "Default")
      (node (ref "IC2") (pin "25") (pinfunction "P2.4/A12_25") (pintype "input"))
      (node (ref "R23") (pin "1") (pinfunction "1_1") (pintype "input"))
    )
    (net (code "30") (name "/P2.5") (class "Default")
      (node (ref "IC2") (pin "26") (pinfunction "P2.5/A13_26") (pintype "input"))
      (node (ref "R24") (pin "1") (pinfunction "1_1") (pintype "input"))
    )
    (net (code "31") (name "/P2.6") (class "Default")
      (node (ref "IC2") (pin "27") (pinfunction "P2.6/A14_27") (pintype "input"))
      (node (ref "R25") (pin "1") (pinfunction "1_1") (pintype "input"))
    )
    (net (code "32") (name "/P2.7") (class "Default")
      (node (ref "IC2") (pin "28") (pinfunction "P2.7/A15_28") (pintype "input"))
      (node (ref "R26") (pin "1") (pinfunction "1_1") (pintype "input"))
    )
    (net (code "33") (name "/P03") (class "Default")
      (node (ref "IC2") (pin "36") (pinfunction "P0.3_36") (pintype "input"))
      (node (ref "R13") (pin "1") (pinfunction "1_1") (pintype "input"))
    )
    (net (code "34") (name "/P3.4") (class "Default")
      (node (ref "IC2") (pin "14") (pinfunction "CLKOUT0/INT#/T0/P3.4_14") (pintype "input"))
      (node (ref "R27") (pin "1") (pinfunction "1_1") (pintype "input"))
    )
    (net (code "35") (name "/P3.5") (class "Default")
      (node (ref "IC2") (pin "15") (pinfunction "CLKOUT1/INT#/T1/P3.5_15") (pintype "input"))
      (node (ref "R28") (pin "1") (pinfunction "1_1") (pintype "input"))
    )
    (net (code "36") (name "/P3.6") (class "Default")
      (node (ref "IC2") (pin "16") (pinfunction "WR#/P3.6_16") (pintype "input"))
      (node (ref "R29") (pin "1") (pinfunction "1_1") (pintype "input"))
    )
    (net (code "37") (name "/P3.7") (class "Default")
      (node (ref "IC2") (pin "17") (pinfunction "RD#/P3.7_17") (pintype "input"))
      (node (ref "R30") (pin "1") (pinfunction "1_1") (pintype "input"))
    )
    (net (code "38") (name "/P04") (class "Default")
      (node (ref "IC2") (pin "35") (pinfunction "P0.4_35") (pintype "input"))
      (node (ref "R14") (pin "1") (pinfunction "1_1") (pintype "input"))
    )
    (net (code "39") (name "/P05") (class "Default")
      (node (ref "IC2") (pin "34") (pinfunction "P0.5_34") (pintype "input"))
      (node (ref "R15") (pin "1") (pinfunction "1_1") (pintype "input"))
    )
    (net (code "40") (name "/P06") (class "Default")
      (node (ref "IC2") (pin "33") (pinfunction "P0.6_33") (pintype "input"))
      (node (ref "R16") (pin "1") (pinfunction "1_1") (pintype "input"))
    )
    (net (code "41") (name "/P07") (class "Default")
      (node (ref "IC2") (pin "32") (pinfunction "P0.7_32") (pintype "input"))
      (node (ref "R17") (pin "1") (pinfunction "1_1") (pintype "input"))
    )
    (net (code "42") (name "/RXD") (class "Default")
      (node (ref "IC2") (pin "10") (pinfunction "INT#/RXD/P3.0_10") (pintype "input"))
      (node (ref "J4") (pin "2") (pinfunction "2_2") (pintype "input"))
    )
    (net (code "43") (name "/TEMP") (class "Default")
      (node (ref "IC2") (pin "13") (pinfunction "INT1#/P3.3_13") (pintype "input"))
      (node (ref "IC3") (pin "2") (pinfunction "DQ_2") (pintype "input"))
      (node (ref "R34") (pin "2") (pinfunction "2_2") (pintype "input"))
      (node (ref "TP9") (pin "1") (pinfunction "1_1") (pintype "input"))
    )
    (net (code "44") (name "/TXD") (class "Default")
      (node (ref "IC2") (pin "11") (pinfunction "TXD/P3.1_11") (pintype "input"))
      (node (ref "J4") (pin "1") (pinfunction "1_1") (pintype "input"))
    )
    (net (code "45") (name "GND") (class "Default")
      (node (ref "C10") (pin "2") (pinfunction "2_2") (pintype "input"))
      (node (ref "C11") (pin "2") (pinfunction "2_2") (pintype "input"))
      (node (ref "C12") (pin "1") (pinfunction "1_1") (pintype "input"))
      (node (ref "C13") (pin "2") (pinfunction "2_2") (pintype "input"))
      (node (ref "C14") (pin "1") (pinfunction "1_1") (pintype "input"))
      (node (ref "C15") (pin "1") (pinfunction "1_1") (pintype "input"))
      (node (ref "C16") (pin "2") (pinfunction "2_2") (pintype "input"))
      (node (ref "C6") (pin "1") (pinfunction "1_1") (pintype "input"))
      (node (ref "C7") (pin "1") (pinfunction "1_1") (pintype "input"))
      (node (ref "C9") (pin "1") (pinfunction "1_1") (pintype "input"))
      (node (ref "IC2") (pin "20") (pinfunction "GND_20") (pintype "input"))
      (node (ref "IC3") (pin "1") (pinfunction "GND_1") (pintype "input"))
      (node (ref "IC4") (pin "3") (pinfunction "GND_3") (pintype "input"))
      (node (ref "IC5") (pin "2") (pinfunction "GND_2") (pintype "input"))
      (node (ref "J10") (pin "1") (pinfunction "1_1") (pintype "input"))
      (node (ref "J11") (pin "1") (pinfunction "1_1") (pintype "input"))
      (node (ref "J3") (pin "2") (pinfunction "2_2") (pintype "input"))
      (node (ref "J4") (pin "3") (pinfunction "3_3") (pintype "input"))
      (node (ref "J5") (pin "3") (pinfunction "3_3") (pintype "input"))
      (node (ref "J8") (pin "1") (pinfunction "1_1") (pintype "input"))
      (node (ref "J9") (pin "1") (pinfunction "1_1") (pintype "input"))
      (node (ref "JK1") (pin "3") (pinfunction "3_3") (pintype "input"))
      (node (ref "JK2") (pin "3") (pinfunction "3_3") (pintype "input"))
      (node (ref "LED10") (pin "2") (pinfunction "2_2") (pintype "input"))
      (node (ref "LS1") (pin "3") (pinfunction "3_3") (pintype "input"))
      (node (ref "R18") (pin "1") (pinfunction "1_1") (pintype "input"))
      (node (ref "TP16") (pin "1") (pinfunction "1_1") (pintype "input"))
      (node (ref "TP17") (pin "1") (pinfunction "1_1") (pintype "input"))
      (node (ref "TP18") (pin "1") (pinfunction "1_1") (pintype "input"))
      (node (ref "VT2") (pin "2") (pinfunction "2_2") (pintype "input"))
      (node (ref "VT3") (pin "2") (pinfunction "2_2") (pintype "input"))
      (node (ref "VT4") (pin "1") (pinfunction "E_1") (pintype "input"))
      (node (ref "VT9") (pin "2") (pinfunction "2_2") (pintype "input"))
    )
    (net (code "46") (name "Net-(BEEP1-Pad2)") (class "Default")
      (node (ref "BEEP1") (pin "2") (pinfunction "2_2") (pintype "input"))
      (node (ref "VT9") (pin "3") (pinfunction "3_3") (pintype "input"))
    )
    (net (code "47") (name "Net-(IC2-P4.7{slash}RST)") (class "Default")
      (node (ref "C8") (pin "2") (pinfunction "2_2") (pintype "input"))
      (node (ref "IC2") (pin "9") (pinfunction "P4.7/RST_9") (pintype "input"))
      (node (ref "R18") (pin "2") (pinfunction "2_2") (pintype "input"))
      (node (ref "RST") (pin "4") (pinfunction "D_4") (pintype "input"))
    )
    (net (code "48") (name "Net-(IC2-TXD2{slash}CPP0{slash}ADC3{slash}P1.3)") (class "Default")
      (node (ref "IC2") (pin "4") (pinfunction "TXD2/CPP0/ADC3/P1.3_4") (pintype "input"))
      (node (ref "S2") (pin "1") (pinfunction "1_1") (pintype "input"))
      (node (ref "S2") (pin "2") (pinfunction "2_2") (pintype "input"))
      (node (ref "S2") (pin "3") (pinfunction "3_3") (pintype "input"))
      (node (ref "S2") (pin "4") (pinfunction "4_4") (pintype "input"))
      (node (ref "S2") (pin "5") (pinfunction "5_5") (pintype "input"))
      (node (ref "S2") (pin "6") (pinfunction "6_6") (pintype "input"))
      (node (ref "S2") (pin "7") (pinfunction "7_7") (pintype "input"))
      (node (ref "S2") (pin "8") (pinfunction "8_8") (pintype "input"))
    )
    (net (code "49") (name "Net-(IC2-XTAL1)") (class "Default")
      (node (ref "C6") (pin "2") (pinfunction "2_2") (pintype "input"))
      (node (ref "IC2") (pin "19") (pinfunction "XTAL1_19") (pintype "input"))
      (node (ref "TP10") (pin "1") (pinfunction "1_1") (pintype "input"))
      (node (ref "Y1") (pin "1") (pinfunction "OSC1_1") (pintype "input"))
    )
    (net (code "50") (name "Net-(IC2-XTAL2)") (class "Default")
      (node (ref "C7") (pin "2") (pinfunction "2_2") (pintype "input"))
      (node (ref "IC2") (pin "18") (pinfunction "XTAL2_18") (pintype "input"))
      (node (ref "Y1") (pin "2") (pinfunction "OSC2_2") (pintype "input"))
    )
    (net (code "51") (name "Net-(IC5-VIN)") (class "Default")
      (node (ref "C10") (pin "1") (pinfunction "1_1") (pintype "input"))
      (node (ref "C9") (pin "2") (pinfunction "2_2") (pintype "input"))
      (node (ref "IC5") (pin "1") (pinfunction "VIN_1") (pintype "input"))
      (node (ref "VD12") (pin "1") (pinfunction "1_1") (pintype "input"))
    )
    (net (code "52") (name "Net-(JK1-Pad1)") (class "Default")
      (node (ref "JK1") (pin "1") (pinfunction "1_1") (pintype "input"))
      (node (ref "VD7") (pin "2") (pinfunction "2_2") (pintype "input"))
      (node (ref "VT2") (pin "3") (pinfunction "3_3") (pintype "input"))
    )
    (net (code "53") (name "Net-(JK1-Pad5)") (class "Default")
      (node (ref "JK1") (pin "5") (pinfunction "5_5") (pintype "input"))
      (node (ref "LED12") (pin "2") (pinfunction "2_2") (pintype "input"))
      (node (ref "LS3") (pin "1") (pinfunction "1_1") (pintype "input"))
      (node (ref "R37") (pin "1") (pinfunction "1_1") (pintype "input"))
    )
    (net (code "54") (name "Net-(JK2-Pad1)") (class "Default")
      (node (ref "JK2") (pin "1") (pinfunction "1_1") (pintype "input"))
      (node (ref "VD8") (pin "2") (pinfunction "2_2") (pintype "input"))
      (node (ref "VT3") (pin "3") (pinfunction "3_3") (pintype "input"))
    )
    (net (code "55") (name "Net-(JK2-Pad5)") (class "Default")
      (node (ref "JK2") (pin "5") (pinfunction "5_5") (pintype "input"))
      (node (ref "LED11") (pin "2") (pinfunction "2_2") (pintype "input"))
      (node (ref "LS3") (pin "2") (pinfunction "2_2") (pintype "input"))
      (node (ref "R38") (pin "2") (pinfunction "2_2") (pintype "input"))
    )
    (net (code "56") (name "Net-(LED2-Pad1)") (class "Default")
      (node (ref "LED2") (pin "1") (pinfunction "1_1") (pintype "input"))
      (node (ref "LED3") (pin "1") (pinfunction "1_1") (pintype "input"))
      (node (ref "LED4") (pin "1") (pinfunction "1_1") (pintype "input"))
      (node (ref "LED5") (pin "1") (pinfunction "1_1") (pintype "input"))
      (node (ref "LED6") (pin "1") (pinfunction "1_1") (pintype "input"))
      (node (ref "LED7") (pin "1") (pinfunction "1_1") (pintype "input"))
      (node (ref "LED8") (pin "1") (pinfunction "1_1") (pintype "input"))
      (node (ref "LED9") (pin "1") (pinfunction "1_1") (pintype "input"))
      (node (ref "VT8") (pin "3") (pinfunction "3_3") (pintype "input"))
    )
    (net (code "57") (name "Net-(LED10-Pad1)") (class "Default")
      (node (ref "LED10") (pin "1") (pinfunction "1_1") (pintype "input"))
      (node (ref "R36") (pin "2") (pinfunction "2_2") (pintype "input"))
    )
    (net (code "58") (name "Net-(LED11-Pad1)") (class "Default")
      (node (ref "LED11") (pin "1") (pinfunction "1_1") (pintype "input"))
      (node (ref "VD13") (pin "1") (pinfunction "1_1") (pintype "input"))
    )
    (net (code "59") (name "Net-(LED12-Pad1)") (class "Default")
      (node (ref "LED12") (pin "1") (pinfunction "1_1") (pintype "input"))
      (node (ref "VD14") (pin "1") (pinfunction "1_1") (pintype "input"))
    )
    (net (code "60") (name "Net-(LS1-Pad1)") (class "Default")
      (node (ref "LS1") (pin "1") (pinfunction "1_1") (pintype "input"))
      (node (ref "R39") (pin "1") (pinfunction "1_1") (pintype "input"))
    )
    (net (code "61") (name "Net-(R10-Pad2)") (class "Default")
      (node (ref "R10") (pin "2") (pinfunction "2_2") (pintype "input"))
      (node (ref "S2") (pin "16") (pinfunction "16_16") (pintype "input"))
    )
    (net (code "62") (name "Net-(R11-Pad2)") (class "Default")
      (node (ref "R11") (pin "2") (pinfunction "2_2") (pintype "input"))
      (node (ref "S2") (pin "15") (pinfunction "15_15") (pintype "input"))
    )
    (net (code "63") (name "Net-(R12-Pad2)") (class "Default")
      (node (ref "R12") (pin "2") (pinfunction "2_2") (pintype "input"))
      (node (ref "S2") (pin "14") (pinfunction "14_14") (pintype "input"))
    )
    (net (code "64") (name "Net-(R13-Pad2)") (class "Default")
      (node (ref "R13") (pin "2") (pinfunction "2_2") (pintype "input"))
      (node (ref "S2") (pin "13") (pinfunction "13_13") (pintype "input"))
    )
    (net (code "65") (name "Net-(R14-Pad2)") (class "Default")
      (node (ref "R14") (pin "2") (pinfunction "2_2") (pintype "input"))
      (node (ref "S2") (pin "12") (pinfunction "12_12") (pintype "input"))
    )
    (net (code "66") (name "Net-(R15-Pad2)") (class "Default")
      (node (ref "R15") (pin "2") (pinfunction "2_2") (pintype "input"))
      (node (ref "S2") (pin "11") (pinfunction "11_11") (pintype "input"))
    )
    (net (code "67") (name "Net-(R16-Pad2)") (class "Default")
      (node (ref "R16") (pin "2") (pinfunction "2_2") (pintype "input"))
      (node (ref "S2") (pin "10") (pinfunction "10_10") (pintype "input"))
    )
    (net (code "68") (name "Net-(R17-Pad2)") (class "Default")
      (node (ref "R17") (pin "2") (pinfunction "2_2") (pintype "input"))
      (node (ref "S2") (pin "9") (pinfunction "9_9") (pintype "input"))
    )
    (net (code "69") (name "Net-(R30-Pad2)") (class "Default")
      (node (ref "R30") (pin "2") (pinfunction "2_2") (pintype "input"))
      (node (ref "VT8") (pin "1") (pinfunction "1_1") (pintype "input"))
    )
    (net (code "70") (name "Net-(R31-Pad1)") (class "Default")
      (node (ref "R31") (pin "1") (pinfunction "1_1") (pintype "input"))
      (node (ref "VD9") (pin "1") (pinfunction "1_1") (pintype "input"))
    )
    (net (code "71") (name "Net-(R31-Pad2)") (class "Default")
      (node (ref "R31") (pin "2") (pinfunction "2_2") (pintype "input"))
      (node (ref "VT2") (pin "1") (pinfunction "1_1") (pintype "input"))
    )
    (net (code "72") (name "Net-(R32-Pad1)") (class "Default")
      (node (ref "R32") (pin "1") (pinfunction "1_1") (pintype "input"))
      (node (ref "VD10") (pin "1") (pinfunction "1_1") (pintype "input"))
    )
    (net (code "73") (name "Net-(R32-Pad2)") (class "Default")
      (node (ref "R32") (pin "2") (pinfunction "2_2") (pintype "input"))
      (node (ref "VT3") (pin "1") (pinfunction "1_1") (pintype "input"))
    )
    (net (code "74") (name "Net-(R33-Pad1)") (class "Default")
      (node (ref "R33") (pin "1") (pinfunction "1_1") (pintype "input"))
      (node (ref "VD11") (pin "1") (pinfunction "1_1") (pintype "input"))
    )
    (net (code "75") (name "Net-(R35-Pad2)") (class "Default")
      (node (ref "R35") (pin "2") (pinfunction "2_2") (pintype "input"))
      (node (ref "VT9") (pin "1") (pinfunction "1_1") (pintype "input"))
    )
    (net (code "76") (name "Net-(R37-Pad2)") (class "Default")
      (node (ref "R37") (pin "2") (pinfunction "2_2") (pintype "input"))
      (node (ref "VD13") (pin "2") (pinfunction "2_2") (pintype "input"))
    )
    (net (code "77") (name "Net-(R38-Pad1)") (class "Default")
      (node (ref "R38") (pin "1") (pinfunction "1_1") (pintype "input"))
      (node (ref "VD14") (pin "2") (pinfunction "2_2") (pintype "input"))
    )
    (net (code "78") (name "Net-(VT4-B)") (class "Default")
      (node (ref "R33") (pin "2") (pinfunction "2_2") (pintype "input"))
      (node (ref "VT4") (pin "3") (pinfunction "B_3") (pintype "input"))
    )
    (net (code "79") (name "Net-(VT4-C)") (class "Default")
      (node (ref "CON2") (pin "2") (pinfunction "2_2") (pintype "input"))
      (node (ref "VT4") (pin "2") (pinfunction "C_2") (pintype "input"))
    )
    (net (code "80") (name "Net-(VT5-B)") (class "Default")
      (node (ref "R27") (pin "2") (pinfunction "2_2") (pintype "input"))
      (node (ref "VT5") (pin "1") (pinfunction "B_1") (pintype "input"))
    )
    (net (code "81") (name "Net-(VT6-B)") (class "Default")
      (node (ref "R28") (pin "2") (pinfunction "2_2") (pintype "input"))
      (node (ref "VT6") (pin "1") (pinfunction "B_1") (pintype "input"))
    )
    (net (code "82") (name "Net-(VT7-B)") (class "Default")
      (node (ref "R29") (pin "2") (pinfunction "2_2") (pintype "input"))
      (node (ref "VT7") (pin "1") (pinfunction "B_1") (pintype "input"))
    )
    (net (code "83") (name "unconnected-(IC2-ALE{slash}P4.5-Pad30)") (class "Default")
      (node (ref "IC2") (pin "30") (pinfunction "ALE/P4.5_30") (pintype "input+no_connect"))
    )
    (net (code "84") (name "unconnected-(IC2-NA{slash}P4.4-Pad29)") (class "Default")
      (node (ref "IC2") (pin "29") (pinfunction "NA/P4.4_29") (pintype "input+no_connect"))
    )
    (net (code "85") (name "unconnected-(RST-B-Pad2)") (class "Default")
      (node (ref "RST") (pin "2") (pinfunction "B_2") (pintype "input+no_connect"))
    )
    (net (code "86") (name "unconnected-(RST-C-Pad3)") (class "Default")
      (node (ref "RST") (pin "3") (pinfunction "C_3") (pintype "input+no_connect"))
    )
  )
)
